# cartridge.net
KiCad netlist of a schematic drawn in EAGLE
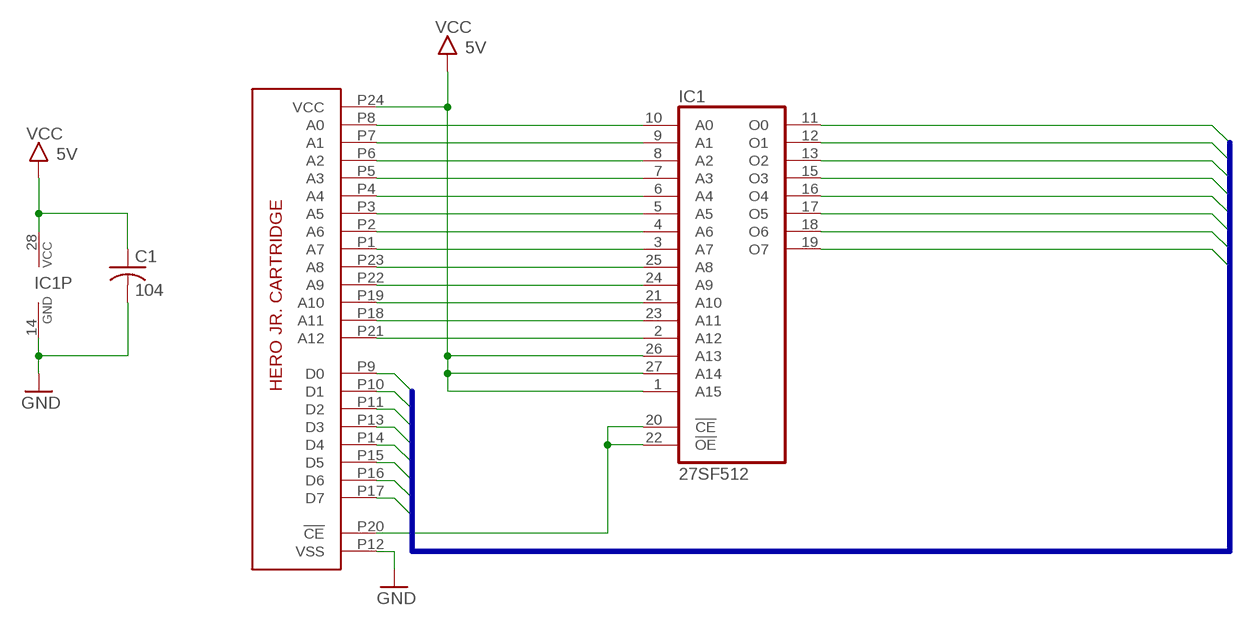
[diagram p0: schematic, sheet 1]

(export (version "E")
  (design (tool "Eeschema 10.0.6"))
  (components
    (comp (ref "C1")
      (value "104")
      (footprint "eagle-import:C050-024X044")
      (libsource (lib "eagle-import") (part "C-US050-024X044"))
    )
    (comp (ref "IC1")
      (value "27SF512")
      (footprint "eagle-import:DIL28")
      (libsource (lib "eagle-import") (part "27512"))
    )
    (comp (ref "U$1")
      (value "HEROJRCART")
      (footprint "eagle-import:HEROJRCART")
      (libsource (lib "eagle-import") (part "HEROJRCART"))
    )
  )
  (nets
    (net (code "1") (name "/D0") (class "Default")
      (node (ref "IC1") (pin "11") (pinfunction "O0_11") (pintype "tri_state"))
      (node (ref "U$1") (pin "P9") (pinfunction "D0_P9") (pintype "bidirectional"))
    )
    (net (code "2") (name "/D1") (class "Default")
      (node (ref "IC1") (pin "12") (pinfunction "O1_12") (pintype "tri_state"))
      (node (ref "U$1") (pin "P10") (pinfunction "D1_P10") (pintype "bidirectional"))
    )
    (net (code "3") (name "/D2") (class "Default")
      (node (ref "IC1") (pin "13") (pinfunction "O2_13") (pintype "tri_state"))
      (node (ref "U$1") (pin "P11") (pinfunction "D2_P11") (pintype "bidirectional"))
    )
    (net (code "4") (name "/D3") (class "Default")
      (node (ref "IC1") (pin "15") (pinfunction "O3_15") (pintype "tri_state"))
      (node (ref "U$1") (pin "P13") (pinfunction "D3_P13") (pintype "bidirectional"))
    )
    (net (code "5") (name "/D4") (class "Default")
      (node (ref "IC1") (pin "16") (pinfunction "O4_16") (pintype "tri_state"))
      (node (ref "U$1") (pin "P14") (pinfunction "D4_P14") (pintype "bidirectional"))
    )
    (net (code "6") (name "/D5") (class "Default")
      (node (ref "IC1") (pin "17") (pinfunction "O5_17") (pintype "tri_state"))
      (node (ref "U$1") (pin "P15") (pinfunction "D5_P15") (pintype "bidirectional"))
    )
    (net (code "7") (name "/D6") (class "Default")
      (node (ref "IC1") (pin "18") (pinfunction "O6_18") (pintype "tri_state"))
      (node (ref "U$1") (pin "P16") (pinfunction "D6_P16") (pintype "bidirectional"))
    )
    (net (code "8") (name "/D7") (class "Default")
      (node (ref "IC1") (pin "19") (pinfunction "O7_19") (pintype "tri_state"))
      (node (ref "U$1") (pin "P17") (pinfunction "D7_P17") (pintype "bidirectional"))
    )
    (net (code "9") (name "5V") (class "Default")
      (node (ref "C1") (pin "1") (pinfunction "1_1") (pintype "passive"))
      (node (ref "IC1") (pin "1") (pinfunction "A15_1") (pintype "input"))
      (node (ref "IC1") (pin "26") (pinfunction "A13_26") (pintype "input"))
      (node (ref "IC1") (pin "27") (pinfunction "A14_27") (pintype "input"))
      (node (ref "IC1") (pin "28") (pinfunction "VCC_28") (pintype "power_in"))
      (node (ref "U$1") (pin "P24") (pinfunction "VCC_P24") (pintype "bidirectional"))
    )
    (net (code "10") (name "GND") (class "Default")
      (node (ref "C1") (pin "2") (pinfunction "2_2") (pintype "passive"))
      (node (ref "IC1") (pin "14") (pinfunction "GND_14") (pintype "power_in"))
      (node (ref "U$1") (pin "P12") (pinfunction "VSS_P12") (pintype "bidirectional"))
    )
    (net (code "11") (name "Net-(IC1A-A0)") (class "Default")
      (node (ref "IC1") (pin "10") (pinfunction "A0_10") (pintype "input"))
      (node (ref "U$1") (pin "P8") (pinfunction "A0_P8") (pintype "bidirectional"))
    )
    (net (code "12") (name "Net-(IC1A-A1)") (class "Default")
      (node (ref "IC1") (pin "9") (pinfunction "A1_9") (pintype "input"))
      (node (ref "U$1") (pin "P7") (pinfunction "A1_P7") (pintype "bidirectional"))
    )
    (net (code "13") (name "Net-(IC1A-A2)") (class "Default")
      (node (ref "IC1") (pin "8") (pinfunction "A2_8") (pintype "input"))
      (node (ref "U$1") (pin "P6") (pinfunction "A2_P6") (pintype "bidirectional"))
    )
    (net (code "14") (name "Net-(IC1A-A3)") (class "Default")
      (node (ref "IC1") (pin "7") (pinfunction "A3_7") (pintype "input"))
      (node (ref "U$1") (pin "P5") (pinfunction "A3_P5") (pintype "bidirectional"))
    )
    (net (code "15") (name "Net-(IC1A-A4)") (class "Default")
      (node (ref "IC1") (pin "6") (pinfunction "A4_6") (pintype "input"))
      (node (ref "U$1") (pin "P4") (pinfunction "A4_P4") (pintype "bidirectional"))
    )
    (net (code "16") (name "Net-(IC1A-A5)") (class "Default")
      (node (ref "IC1") (pin "5") (pinfunction "A5_5") (pintype "input"))
      (node (ref "U$1") (pin "P3") (pinfunction "A5_P3") (pintype "bidirectional"))
    )
    (net (code "17") (name "Net-(IC1A-A6)") (class "Default")
      (node (ref "IC1") (pin "4") (pinfunction "A6_4") (pintype "input"))
      (node (ref "U$1") (pin "P2") (pinfunction "A6_P2") (pintype "bidirectional"))
    )
    (net (code "18") (name "Net-(IC1A-A7)") (class "Default")
      (node (ref "IC1") (pin "3") (pinfunction "A7_3") (pintype "input"))
      (node (ref "U$1") (pin "P1") (pinfunction "A7_P1") (pintype "bidirectional"))
    )
    (net (code "19") (name "Net-(IC1A-A8)") (class "Default")
      (node (ref "IC1") (pin "25") (pinfunction "A8_25") (pintype "input"))
      (node (ref "U$1") (pin "P23") (pinfunction "A8_P23") (pintype "bidirectional"))
    )
    (net (code "20") (name "Net-(IC1A-A9)") (class "Default")
      (node (ref "IC1") (pin "24") (pinfunction "A9_24") (pintype "input"))
      (node (ref "U$1") (pin "P22") (pinfunction "A9_P22") (pintype "bidirectional"))
    )
    (net (code "21") (name "Net-(IC1A-A10)") (class "Default")
      (node (ref "IC1") (pin "21") (pinfunction "A10_21") (pintype "input"))
      (node (ref "U$1") (pin "P19") (pinfunction "A10_P19") (pintype "bidirectional"))
    )
    (net (code "22") (name "Net-(IC1A-A11)") (class "Default")
      (node (ref "IC1") (pin "23") (pinfunction "A11_23") (pintype "input"))
      (node (ref "U$1") (pin "P18") (pinfunction "A11_P18") (pintype "bidirectional"))
    )
    (net (code "23") (name "Net-(IC1A-A12)") (class "Default")
      (node (ref "IC1") (pin "2") (pinfunction "A12_2") (pintype "input"))
      (node (ref "U$1") (pin "P21") (pinfunction "A12_P21") (pintype "bidirectional"))
    )
    (net (code "24") (name "Net-(IC1A-~{CE})") (class "Default")
      (node (ref "IC1") (pin "20") (pinfunction "~{CE}_20") (pintype "input"))
      (node (ref "IC1") (pin "22") (pinfunction "~{OE}_22") (pintype "input"))
      (node (ref "U$1") (pin "P20") (pinfunction "~{CE}_P20") (pintype "bidirectional"))
    )
  )
)
